# ring_v3.net
KiCad netlist of a schematic drawn in Altium Designer
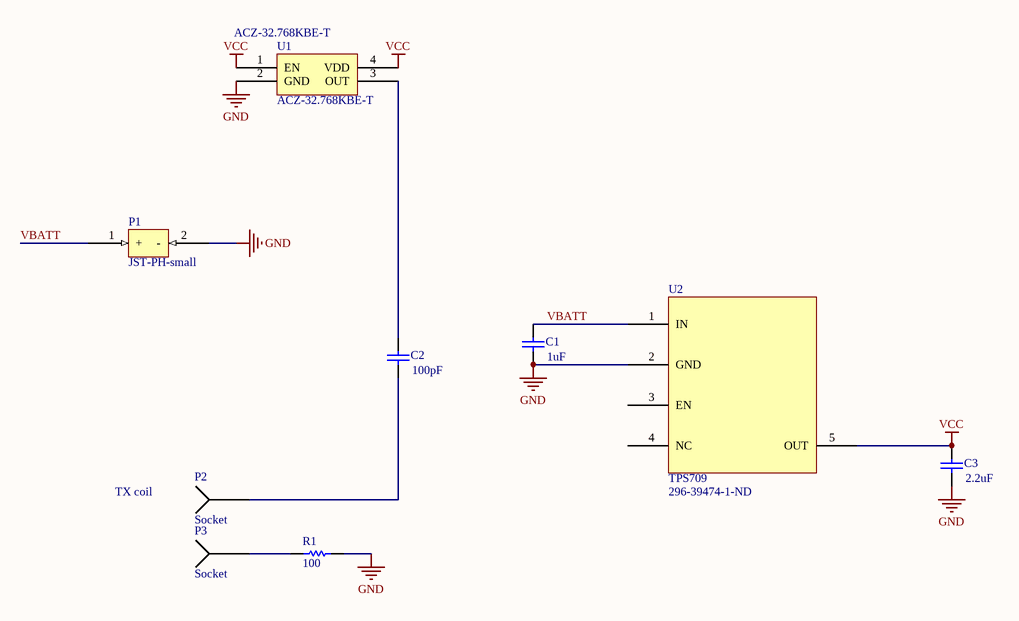
[diagram p0: ring_v3.SchDoc]

(export (version "E")
  (design (tool "Eeschema 10.0.6"))
  (components
    (comp (ref "C1")
      (value "1uF")
      (footprint "0402")
      (description "Ceramic Capacitor (Surface Mount)")
      (fields (field (name "MANUFACTURER") "Generic Ceramic Chip Cap (TBD)") (field (name "Comment") "Cap"))
      (libsource (lib "maglib") (part "Cap"))
    )
    (comp (ref "C2")
      (value "100pF")
      (footprint "0402")
      (description "Ceramic Capacitor (Surface Mount)")
      (fields (field (name "MANUFACTURER") "Generic Ceramic Chip Cap (TBD)") (field (name "Comment") "Cap"))
      (libsource (lib "maglib") (part "Cap"))
    )
    (comp (ref "C3")
      (value "2.2uF")
      (footprint "0402")
      (description "Ceramic Capacitor (Surface Mount)")
      (fields (field (name "MANUFACTURER") "Generic Ceramic Chip Cap (TBD)") (field (name "Comment") "Cap"))
      (libsource (lib "maglib") (part "Cap"))
    )
    (comp (ref "P1")
      (value "JST-PH-small")
      (footprint "JST-PH-small")
      (libsource (lib "maglib") (part "JST-PH-small"))
    )
    (comp (ref "P2") (value "Socket") (footprint "socket") (libsource (lib "maglib") (part "Socket")))
    (comp (ref "P3") (value "Socket") (footprint "socket") (libsource (lib "maglib") (part "Socket")))
    (comp (ref "R1")
      (value "100")
      (footprint "0402")
      (description "Chip Resistor (Surface Mount)")
      (fields (field (name "MANUFACTURER") "Generic Chip Res (TBD)") (field (name "Comment") "Res"))
      (libsource (lib "maglib") (part "Res"))
    )
    (comp (ref "U1")
      (value "ACZ-32.768KBE-T")
      (footprint "ACZ-32.768KBE-T")
      (description "32.768kHz XO (Standard) CMOS Oscillator 3.3V Enable/Disable 4-SMD, No Lead")
      (fields (field (name "SUPPLIER PART NUMBER 1") "ACZ-32.768KBE-T"))
      (libsource (lib "maglib") (part "ACZ-32.768KBE-T"))
    )
    (comp (ref "U2")
      (value "TPS709")
      (footprint "SOT95P280X145-5N")
      (description "3.3V Ultra low power Voltage Regulator")
      (fields (field (name "SUPPLIER PART NUMBER 1") "296-39474-1-ND"))
      (libsource (lib "maglib") (part "TPS70933"))
    )
  )
  (nets
    (net (code "1") (name "/VBATT") (class "Default")
      (node (ref "C1") (pin "2") (pinfunction "2_2") (pintype "passive"))
      (node (ref "P1") (pin "1") (pinfunction "+_1") (pintype "input"))
      (node (ref "U2") (pin "1") (pinfunction "IN_1") (pintype "passive"))
    )
    (net (code "2") (name "GND") (class "Default")
      (node (ref "C1") (pin "1") (pinfunction "1_1") (pintype "passive"))
      (node (ref "C3") (pin "1") (pinfunction "1_1") (pintype "passive"))
      (node (ref "P1") (pin "2") (pinfunction "-_2") (pintype "input"))
      (node (ref "R1") (pin "2") (pinfunction "2_2") (pintype "passive"))
      (node (ref "U1") (pin "2") (pinfunction "GND_2") (pintype "power_in"))
      (node (ref "U2") (pin "2") (pinfunction "GND_2") (pintype "passive"))
    )
    (net (code "3") (name "Net-(C2-Pad1)") (class "Default")
      (node (ref "C2") (pin "1") (pinfunction "1_1") (pintype "passive"))
      (node (ref "P2") (pin "0") (pinfunction "0_0") (pintype "passive"))
    )
    (net (code "4") (name "Net-(P3-Pad0)") (class "Default")
      (node (ref "P3") (pin "0") (pinfunction "0_0") (pintype "passive"))
      (node (ref "R1") (pin "1") (pinfunction "1_1") (pintype "passive"))
    )
    (net (code "5") (name "Net-(U1-OUT)") (class "Default")
      (node (ref "C2") (pin "2") (pinfunction "2_2") (pintype "passive"))
      (node (ref "U1") (pin "3") (pinfunction "OUT_3") (pintype "passive"))
    )
    (net (code "6") (name "VCC") (class "Default")
      (node (ref "C3") (pin "2") (pinfunction "2_2") (pintype "passive"))
      (node (ref "U1") (pin "1") (pinfunction "EN_1") (pintype "passive"))
      (node (ref "U1") (pin "4") (pinfunction "VDD_4") (pintype "power_in"))
      (node (ref "U2") (pin "5") (pinfunction "OUT_5") (pintype "passive"))
    )
    (net (code "7") (name "unconnected-(U2-EN-Pad3)") (class "Default")
      (node (ref "U2") (pin "3") (pinfunction "EN_3") (pintype "passive"))
    )
    (net (code "8") (name "unconnected-(U2-NC-Pad4)") (class "Default")
      (node (ref "U2") (pin "4") (pinfunction "NC_4") (pintype "passive"))
    )
  )
)
